# untitled.net
KiCad netlist of a schematic drawn in EAGLE
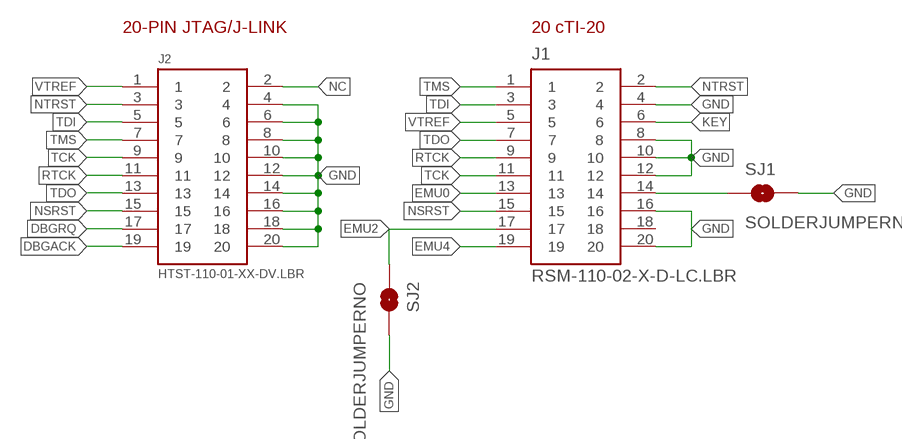
[diagram p0: schematic, sheet 1]

(export (version "E")
  (design (tool "Eeschema 10.0.6"))
  (components
    (comp (ref "J1")
      (value "RSM-110-02-X-D-LC.LBR")
      (footprint "eagle-import:RSM-110-02-X-D-LC.LBR")
      (libsource (lib "eagle-import") (part "RSM-110-02-X-D-LC.LBR"))
    )
    (comp (ref "J2")
      (value "HTST-110-01-XX-DV.LBR")
      (footprint "eagle-import:HTST-110-01-XX-DV.LBR")
      (libsource (lib "eagle-import") (part "HTST-110-01-XX-DV.LBR"))
    )
    (comp (ref "SJ1")
      (value "SOLDERJUMPERNO")
      (footprint "eagle-import:SJ_2S-NO")
      (libsource (lib "eagle-import") (part "SOLDERJUMPERNO"))
    )
    (comp (ref "SJ2")
      (value "SOLDERJUMPERNO")
      (footprint "eagle-import:SJ_2S-NO")
      (libsource (lib "eagle-import") (part "SOLDERJUMPERNO"))
    )
  )
  (nets
    (net (code "1") (name "DBGACK") (class "Default")
      (node (ref "J2") (pin "19") (pinfunction "19_19") (pintype "bidirectional"))
    )
    (net (code "2") (name "DBGRQ") (class "Default")
      (node (ref "J2") (pin "17") (pinfunction "17_17") (pintype "bidirectional"))
    )
    (net (code "3") (name "EMU0") (class "Default")
      (node (ref "J1") (pin "13") (pinfunction "13_13") (pintype "bidirectional"))
    )
    (net (code "4") (name "EMU2") (class "Default")
      (node (ref "J1") (pin "17") (pinfunction "17_17") (pintype "bidirectional"))
      (node (ref "SJ2") (pin "1") (pinfunction "1_1") (pintype "passive"))
    )
    (net (code "5") (name "EMU4") (class "Default")
      (node (ref "J1") (pin "19") (pinfunction "19_19") (pintype "bidirectional"))
    )
    (net (code "6") (name "GND") (class "Default")
      (node (ref "J1") (pin "10") (pinfunction "10_10") (pintype "bidirectional"))
      (node (ref "J1") (pin "12") (pinfunction "12_12") (pintype "bidirectional"))
      (node (ref "J1") (pin "16") (pinfunction "16_16") (pintype "bidirectional"))
      (node (ref "J1") (pin "20") (pinfunction "20_20") (pintype "bidirectional"))
      (node (ref "J1") (pin "4") (pinfunction "4_4") (pintype "bidirectional"))
      (node (ref "J1") (pin "8") (pinfunction "8_8") (pintype "bidirectional"))
      (node (ref "J2") (pin "10") (pinfunction "10_10") (pintype "bidirectional"))
      (node (ref "J2") (pin "12") (pinfunction "12_12") (pintype "bidirectional"))
      (node (ref "J2") (pin "14") (pinfunction "14_14") (pintype "bidirectional"))
      (node (ref "J2") (pin "16") (pinfunction "16_16") (pintype "bidirectional"))
      (node (ref "J2") (pin "18") (pinfunction "18_18") (pintype "bidirectional"))
      (node (ref "J2") (pin "20") (pinfunction "20_20") (pintype "bidirectional"))
      (node (ref "J2") (pin "4") (pinfunction "4_4") (pintype "bidirectional"))
      (node (ref "J2") (pin "6") (pinfunction "6_6") (pintype "bidirectional"))
      (node (ref "J2") (pin "8") (pinfunction "8_8") (pintype "bidirectional"))
      (node (ref "SJ1") (pin "2") (pinfunction "2_2") (pintype "passive"))
      (node (ref "SJ2") (pin "2") (pinfunction "2_2") (pintype "passive"))
    )
    (net (code "7") (name "KEY") (class "Default")
      (node (ref "J1") (pin "6") (pinfunction "6_6") (pintype "bidirectional"))
    )
    (net (code "8") (name "NC") (class "Default")
      (node (ref "J2") (pin "2") (pinfunction "2_2") (pintype "bidirectional"))
    )
    (net (code "9") (name "NSRST") (class "Default")
      (node (ref "J1") (pin "15") (pinfunction "15_15") (pintype "bidirectional"))
      (node (ref "J2") (pin "15") (pinfunction "15_15") (pintype "bidirectional"))
    )
    (net (code "10") (name "NTRST") (class "Default")
      (node (ref "J1") (pin "2") (pinfunction "2_2") (pintype "bidirectional"))
      (node (ref "J2") (pin "3") (pinfunction "3_3") (pintype "bidirectional"))
    )
    (net (code "11") (name "Net-(J1-Pad14)") (class "Default")
      (node (ref "J1") (pin "14") (pinfunction "14_14") (pintype "bidirectional"))
      (node (ref "SJ1") (pin "1") (pinfunction "1_1") (pintype "passive"))
    )
    (net (code "12") (name "RTCK") (class "Default")
      (node (ref "J1") (pin "9") (pinfunction "9_9") (pintype "bidirectional"))
      (node (ref "J2") (pin "11") (pinfunction "11_11") (pintype "bidirectional"))
    )
    (net (code "13") (name "TCK") (class "Default")
      (node (ref "J1") (pin "11") (pinfunction "11_11") (pintype "bidirectional"))
      (node (ref "J2") (pin "9") (pinfunction "9_9") (pintype "bidirectional"))
    )
    (net (code "14") (name "TDI") (class "Default")
      (node (ref "J1") (pin "3") (pinfunction "3_3") (pintype "bidirectional"))
      (node (ref "J2") (pin "5") (pinfunction "5_5") (pintype "bidirectional"))
    )
    (net (code "15") (name "TDO") (class "Default")
      (node (ref "J1") (pin "7") (pinfunction "7_7") (pintype "bidirectional"))
      (node (ref "J2") (pin "13") (pinfunction "13_13") (pintype "bidirectional"))
    )
    (net (code "16") (name "TMS") (class "Default")
      (node (ref "J1") (pin "1") (pinfunction "1_1") (pintype "bidirectional"))
      (node (ref "J2") (pin "7") (pinfunction "7_7") (pintype "bidirectional"))
    )
    (net (code "17") (name "VTREF") (class "Default")
      (node (ref "J1") (pin "5") (pinfunction "5_5") (pintype "bidirectional"))
      (node (ref "J2") (pin "1") (pinfunction "1_1") (pintype "bidirectional"))
    )
    (net (code "18") (name "unconnected-(J1-Pad18)") (class "Default")
      (node (ref "J1") (pin "18") (pinfunction "18_18") (pintype "bidirectional"))
    )
  )
)
